# IO_Receiver.net
KiCad netlist of a schematic drawn in Altium Designer
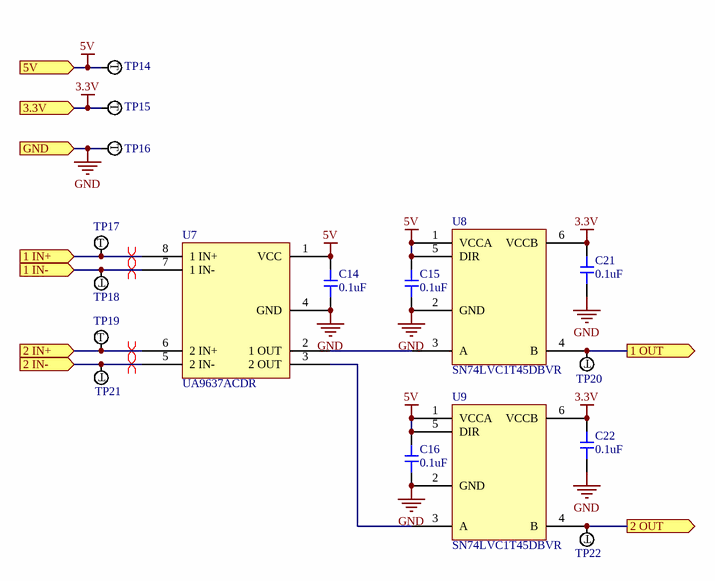
[diagram p0: IO_Receiver.SchDoc]

(export (version "E")
  (design (tool "Eeschema 10.0.6"))
  (components
    (comp (ref "C14")
      (value "0.1uF")
      (footprint "0603-CAP")
      (description "0.1µF ±10% 25V Ceramic Capacitor X7R 0603 (1608 Metric)")
      (fields (field (name "Comment") "CC0603KRX7R8BB104"))
      (libsource (lib "IO_Converter") (part "Capacitor 0.1uF"))
    )
    (comp (ref "C15")
      (value "0.1uF")
      (footprint "0603-CAP")
      (description "0.1µF ±10% 25V Ceramic Capacitor X7R 0603 (1608 Metric)")
      (fields (field (name "Comment") "CC0603KRX7R8BB104"))
      (libsource (lib "IO_Converter") (part "Capacitor 0.1uF"))
    )
    (comp (ref "C16")
      (value "0.1uF")
      (footprint "0603-CAP")
      (description "0.1µF ±10% 25V Ceramic Capacitor X7R 0603 (1608 Metric)")
      (fields (field (name "Comment") "CC0603KRX7R8BB104"))
      (libsource (lib "IO_Converter") (part "Capacitor 0.1uF"))
    )
    (comp (ref "C21")
      (value "0.1uF")
      (footprint "0603-CAP")
      (description "0.1µF ±10% 25V Ceramic Capacitor X7R 0603 (1608 Metric)")
      (fields (field (name "Comment") "CC0603KRX7R8BB104"))
      (libsource (lib "IO_Converter") (part "Capacitor 0.1uF"))
    )
    (comp (ref "C22")
      (value "0.1uF")
      (footprint "0603-CAP")
      (description "0.1µF ±10% 25V Ceramic Capacitor X7R 0603 (1608 Metric)")
      (fields (field (name "Comment") "CC0603KRX7R8BB104"))
      (libsource (lib "IO_Converter") (part "Capacitor 0.1uF"))
    )
    (comp (ref "TP14")
      (value "RCU-0C")
      (footprint "RCU-0C")
      (description "PC TEST POINT NATURAL")
      (libsource (lib "IO_Converter") (part "Test Point"))
    )
    (comp (ref "TP15")
      (value "RCU-0C")
      (footprint "RCU-0C")
      (description "PC TEST POINT NATURAL")
      (libsource (lib "IO_Converter") (part "Test Point"))
    )
    (comp (ref "TP16")
      (value "RCU-0C")
      (footprint "RCU-0C")
      (description "PC TEST POINT NATURAL")
      (libsource (lib "IO_Converter") (part "Test Point"))
    )
    (comp (ref "TP17")
      (value "RCU-0C")
      (footprint "RCU-0C")
      (description "PC TEST POINT NATURAL")
      (libsource (lib "IO_Converter") (part "Test Point"))
    )
    (comp (ref "TP18")
      (value "RCU-0C")
      (footprint "RCU-0C")
      (description "PC TEST POINT NATURAL")
      (libsource (lib "IO_Converter") (part "Test Point"))
    )
    (comp (ref "TP19")
      (value "RCU-0C")
      (footprint "RCU-0C")
      (description "PC TEST POINT NATURAL")
      (libsource (lib "IO_Converter") (part "Test Point"))
    )
    (comp (ref "TP20")
      (value "RCU-0C")
      (footprint "RCU-0C")
      (description "PC TEST POINT NATURAL")
      (libsource (lib "IO_Converter") (part "Test Point"))
    )
    (comp (ref "TP21")
      (value "RCU-0C")
      (footprint "RCU-0C")
      (description "PC TEST POINT NATURAL")
      (libsource (lib "IO_Converter") (part "Test Point"))
    )
    (comp (ref "TP22")
      (value "RCU-0C")
      (footprint "RCU-0C")
      (description "PC TEST POINT NATURAL")
      (libsource (lib "IO_Converter") (part "Test Point"))
    )
    (comp (ref "U7")
      (value "UA9637ACDR")
      (footprint "SOIC127P600X175-8N")
      (description "IC RECEIVER 0/2 8SOIC")
      (libsource (lib "IO_Converter") (part "UA9637ACDR"))
    )
    (comp (ref "U8")
      (value "SN74LVC1T45DBVR")
      (footprint "SOT95P280X145-6N")
      (description "IC TRNSLTR BIDIRECTIONAL SOT23-6")
      (libsource (lib "IO_Converter") (part "SN74LVC1T45DBVR"))
    )
    (comp (ref "U9")
      (value "SN74LVC1T45DBVR")
      (footprint "SOT95P280X145-6N")
      (description "IC TRNSLTR BIDIRECTIONAL SOT23-6")
      (libsource (lib "IO_Converter") (part "SN74LVC1T45DBVR"))
    )
  )
  (nets
    (net (code "1") (name "/1 IN+") (class "Default")
      (node (ref "TP17") (pin "1") (pinfunction "1_1") (pintype "passive"))
      (node (ref "U7") (pin "8") (pinfunction "1_IN+_8") (pintype "passive"))
    )
    (net (code "2") (name "/1 IN-") (class "Default")
      (node (ref "TP18") (pin "1") (pinfunction "1_1") (pintype "passive"))
      (node (ref "U7") (pin "7") (pinfunction "1_IN-_7") (pintype "passive"))
    )
    (net (code "3") (name "/1 OUT") (class "Default")
      (node (ref "TP20") (pin "1") (pinfunction "1_1") (pintype "passive"))
      (node (ref "U8") (pin "4") (pinfunction "B_4") (pintype "passive"))
    )
    (net (code "4") (name "/2 IN+") (class "Default")
      (node (ref "TP19") (pin "1") (pinfunction "1_1") (pintype "passive"))
      (node (ref "U7") (pin "6") (pinfunction "2_IN+_6") (pintype "passive"))
    )
    (net (code "5") (name "/2 IN-") (class "Default")
      (node (ref "TP21") (pin "1") (pinfunction "1_1") (pintype "passive"))
      (node (ref "U7") (pin "5") (pinfunction "2_IN-_5") (pintype "passive"))
    )
    (net (code "6") (name "/2 OUT") (class "Default")
      (node (ref "TP22") (pin "1") (pinfunction "1_1") (pintype "passive"))
      (node (ref "U9") (pin "4") (pinfunction "B_4") (pintype "passive"))
    )
    (net (code "7") (name "3.3V") (class "Default")
      (node (ref "C21") (pin "2") (pinfunction "2_2") (pintype "passive"))
      (node (ref "C22") (pin "2") (pinfunction "2_2") (pintype "passive"))
      (node (ref "TP15") (pin "1") (pinfunction "1_1") (pintype "passive"))
      (node (ref "U8") (pin "6") (pinfunction "VCCB_6") (pintype "passive"))
      (node (ref "U9") (pin "6") (pinfunction "VCCB_6") (pintype "passive"))
    )
    (net (code "8") (name "5V") (class "Default")
      (node (ref "C14") (pin "2") (pinfunction "2_2") (pintype "passive"))
      (node (ref "C15") (pin "2") (pinfunction "2_2") (pintype "passive"))
      (node (ref "C16") (pin "2") (pinfunction "2_2") (pintype "passive"))
      (node (ref "TP14") (pin "1") (pinfunction "1_1") (pintype "passive"))
      (node (ref "U7") (pin "1") (pinfunction "VCC_1") (pintype "passive"))
      (node (ref "U8") (pin "1") (pinfunction "VCCA_1") (pintype "passive"))
      (node (ref "U8") (pin "5") (pinfunction "DIR_5") (pintype "passive"))
      (node (ref "U9") (pin "1") (pinfunction "VCCA_1") (pintype "passive"))
      (node (ref "U9") (pin "5") (pinfunction "DIR_5") (pintype "passive"))
    )
    (net (code "9") (name "GND") (class "Default")
      (node (ref "C14") (pin "1") (pinfunction "1_1") (pintype "passive"))
      (node (ref "C15") (pin "1") (pinfunction "1_1") (pintype "passive"))
      (node (ref "C16") (pin "1") (pinfunction "1_1") (pintype "passive"))
      (node (ref "C21") (pin "1") (pinfunction "1_1") (pintype "passive"))
      (node (ref "C22") (pin "1") (pinfunction "1_1") (pintype "passive"))
      (node (ref "TP16") (pin "1") (pinfunction "1_1") (pintype "passive"))
      (node (ref "U7") (pin "4") (pinfunction "GND_4") (pintype "passive"))
      (node (ref "U8") (pin "2") (pinfunction "GND_2") (pintype "passive"))
      (node (ref "U9") (pin "2") (pinfunction "GND_2") (pintype "passive"))
    )
    (net (code "10") (name "Net-(U7-1_OUT)") (class "Default")
      (node (ref "U7") (pin "2") (pinfunction "1_OUT_2") (pintype "passive"))
      (node (ref "U8") (pin "3") (pinfunction "A_3") (pintype "passive"))
    )
    (net (code "11") (name "Net-(U7-2_OUT)") (class "Default")
      (node (ref "U7") (pin "3") (pinfunction "2_OUT_3") (pintype "passive"))
      (node (ref "U9") (pin "3") (pinfunction "A_3") (pintype "passive"))
    )
  )
)
